# HV_DCDC_4-22-2016.net
KiCad netlist of a schematic drawn in EAGLE
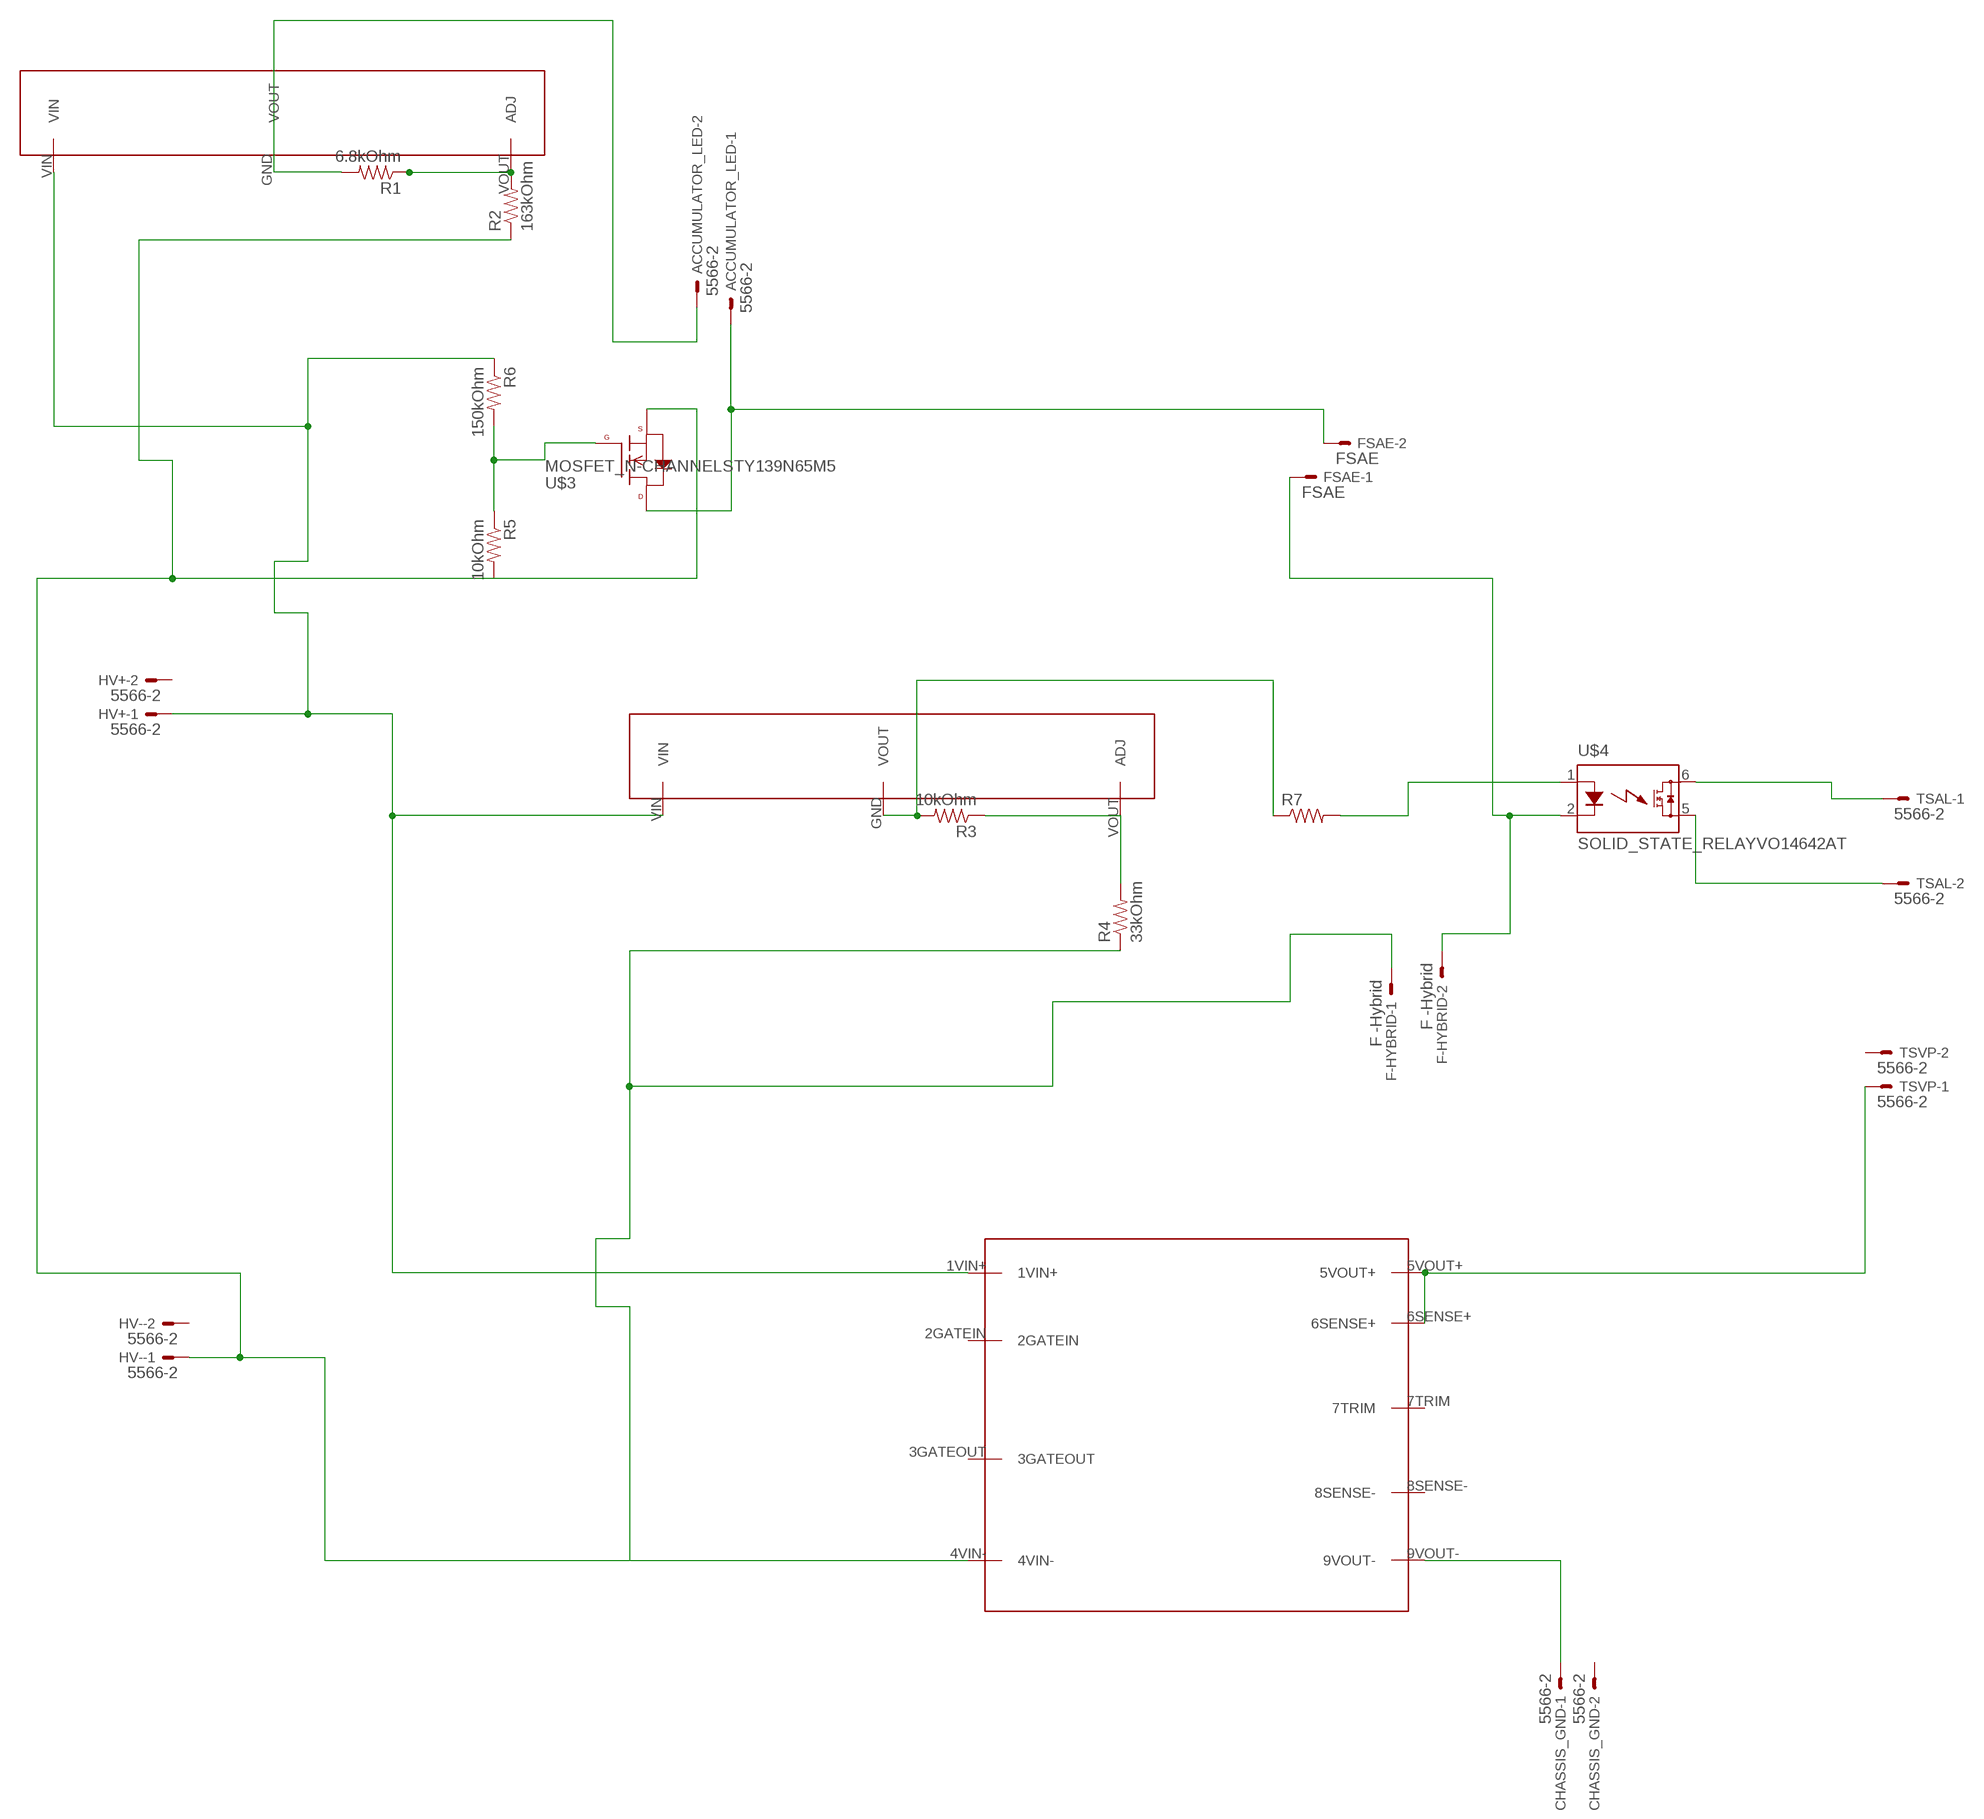
[diagram p0: schematic, sheet 1]

(export (version "E")
  (design (tool "Eeschema 10.0.6"))
  (components
    (comp (ref "ACCUMULATOR_LED")
      (value "5566-2")
      (footprint "eagle-import:5566-2")
      (libsource (lib "eagle-import") (part "5566-2"))
    )
    (comp (ref "CHASSIS_GND")
      (value "5566-2")
      (footprint "eagle-import:5566-2")
      (libsource (lib "eagle-import") (part "5566-2"))
    )
    (comp (ref "F-HYBRID")
      (value "F -Hybrid")
      (footprint "eagle-import:5566-2")
      (libsource (lib "eagle-import") (part "5566-2"))
    )
    (comp (ref "FSAE")
      (value "FSAE")
      (footprint "eagle-import:5566-2")
      (libsource (lib "eagle-import") (part "5566-2"))
    )
    (comp (ref "HV+")
      (value "5566-2")
      (footprint "eagle-import:5566-2")
      (libsource (lib "eagle-import") (part "5566-2"))
    )
    (comp (ref "HV-")
      (value "5566-2")
      (footprint "eagle-import:5566-2")
      (libsource (lib "eagle-import") (part "5566-2"))
    )
    (comp (ref "R1")
      (value "6.8kOhm")
      (footprint "eagle-import:AXIAL-0.3")
      (libsource (lib "eagle-import") (part "RESISTORAXIAL-0.3"))
    )
    (comp (ref "R2")
      (value "163kOhm")
      (footprint "eagle-import:AXIAL-0.3")
      (libsource (lib "eagle-import") (part "RESISTORAXIAL-0.3"))
    )
    (comp (ref "R3")
      (value "10kOhm")
      (footprint "eagle-import:AXIAL-0.3")
      (libsource (lib "eagle-import") (part "RESISTORAXIAL-0.3"))
    )
    (comp (ref "R4")
      (value "33kOhm")
      (footprint "eagle-import:AXIAL-0.3")
      (libsource (lib "eagle-import") (part "RESISTORAXIAL-0.3"))
    )
    (comp (ref "R5")
      (value "10kOhm")
      (footprint "eagle-import:AXIAL-0.3")
      (libsource (lib "eagle-import") (part "RESISTORAXIAL-0.3"))
    )
    (comp (ref "R6")
      (value "150kOhm")
      (footprint "eagle-import:AXIAL-0.3")
      (libsource (lib "eagle-import") (part "RESISTORAXIAL-0.3"))
    )
    (comp (ref "R7")
      (value "RESISTORAXIAL-0.3")
      (footprint "eagle-import:AXIAL-0.3")
      (libsource (lib "eagle-import") (part "RESISTORAXIAL-0.3"))
    )
    (comp (ref "TSAL")
      (value "5566-2")
      (footprint "eagle-import:5566-2")
      (libsource (lib "eagle-import") (part "5566-2"))
    )
    (comp (ref "TSVP")
      (value "5566-2")
      (footprint "eagle-import:5566-2")
      (libsource (lib "eagle-import") (part "5566-2"))
    )
    (comp (ref "U$3")
      (value "MOSFET_N-CHANNELSTY139N65M5")
      (footprint "eagle-import:TO-264_MAX247")
      (libsource (lib "eagle-import") (part "MOSFET_N-CHANNELSTY139N65M5"))
    )
    (comp (ref "U$4")
      (value "SOLID_STATE_RELAYVO14642AT")
      (footprint "eagle-import:DIL06")
      (libsource (lib "eagle-import") (part "SOLID_STATE_RELAYVO14642AT"))
    )
    (comp (ref "U$5")
      (value "HV_DCDC_NEW")
      (footprint "eagle-import:HV_DCDC_NEW")
      (libsource (lib "eagle-import") (part "HV_DCDC_NEW"))
    )
    (comp (ref "U$6")
      (value "HV_LIN_REG")
      (footprint "eagle-import:HV_LIN_REG14MM")
      (libsource (lib "eagle-import") (part "HV_LIN_REG"))
    )
    (comp (ref "U$7")
      (value "HV_LIN_REG")
      (footprint "eagle-import:HV_LIN_REG14MM")
      (libsource (lib "eagle-import") (part "HV_LIN_REG"))
    )
  )
  (nets
    (net (code "1") (name "Net-(ACCUMULATOR_LEDA-S)") (class "Default")
      (node (ref "ACCUMULATOR_LED") (pin "1") (pinfunction "S_1") (pintype "passive"))
      (node (ref "FSAE") (pin "2") (pinfunction "S_2") (pintype "passive"))
      (node (ref "U$3") (pin "P2") (pinfunction "DRAIN_P2") (pintype "passive"))
    )
    (net (code "2") (name "Net-(ACCUMULATOR_LEDB-S)") (class "Default")
      (node (ref "ACCUMULATOR_LED") (pin "2") (pinfunction "S_2") (pintype "passive"))
      (node (ref "R1") (pin "P$2") (pinfunction "2_P$2") (pintype "passive"))
      (node (ref "U$7") (pin "GND") (pinfunction "VOUT_GND") (pintype "bidirectional"))
    )
    (net (code "3") (name "Net-(CHASSIS_GNDA-S)") (class "Default")
      (node (ref "CHASSIS_GND") (pin "1") (pinfunction "S_1") (pintype "passive"))
      (node (ref "U$5") (pin "9VOUT-") (pinfunction "9VOUT-_9VOUT-") (pintype "bidirectional"))
    )
    (net (code "4") (name "Net-(F-HYBRIDA-S)") (class "Default")
      (node (ref "F-HYBRID") (pin "1") (pinfunction "S_1") (pintype "passive"))
      (node (ref "HV-") (pin "1") (pinfunction "S_1") (pintype "passive"))
      (node (ref "R2") (pin "P$1") (pinfunction "1_P$1") (pintype "passive"))
      (node (ref "R4") (pin "P$1") (pinfunction "1_P$1") (pintype "passive"))
      (node (ref "R5") (pin "P$2") (pinfunction "2_P$2") (pintype "passive"))
      (node (ref "U$3") (pin "P3") (pinfunction "SOURCE_P3") (pintype "passive"))
      (node (ref "U$5") (pin "4VIN-") (pinfunction "4VIN-_4VIN-") (pintype "bidirectional"))
    )
    (net (code "5") (name "Net-(F-HYBRIDB-S)") (class "Default")
      (node (ref "F-HYBRID") (pin "2") (pinfunction "S_2") (pintype "passive"))
      (node (ref "FSAE") (pin "1") (pinfunction "S_1") (pintype "passive"))
      (node (ref "U$4") (pin "2") (pinfunction "LED-_2") (pintype "passive"))
    )
    (net (code "6") (name "Net-(HV+A-S)") (class "Default")
      (node (ref "HV+") (pin "1") (pinfunction "S_1") (pintype "passive"))
      (node (ref "R6") (pin "P$1") (pinfunction "1_P$1") (pintype "passive"))
      (node (ref "U$5") (pin "1VIN+") (pinfunction "1VIN+_1VIN+") (pintype "bidirectional"))
      (node (ref "U$6") (pin "VIN") (pinfunction "VIN_VIN") (pintype "bidirectional"))
      (node (ref "U$7") (pin "VIN") (pinfunction "VIN_VIN") (pintype "bidirectional"))
    )
    (net (code "7") (name "Net-(R1-1)") (class "Default")
      (node (ref "R1") (pin "P$1") (pinfunction "1_P$1") (pintype "passive"))
      (node (ref "R2") (pin "P$2") (pinfunction "2_P$2") (pintype "passive"))
      (node (ref "U$7") (pin "VOUT") (pinfunction "ADJ_VOUT") (pintype "bidirectional"))
    )
    (net (code "8") (name "Net-(R3-1)") (class "Default")
      (node (ref "R3") (pin "P$1") (pinfunction "1_P$1") (pintype "passive"))
      (node (ref "R4") (pin "P$2") (pinfunction "2_P$2") (pintype "passive"))
      (node (ref "U$6") (pin "VOUT") (pinfunction "ADJ_VOUT") (pintype "bidirectional"))
    )
    (net (code "9") (name "Net-(R3-2)") (class "Default")
      (node (ref "R3") (pin "P$2") (pinfunction "2_P$2") (pintype "passive"))
      (node (ref "R7") (pin "P$1") (pinfunction "1_P$1") (pintype "passive"))
      (node (ref "U$6") (pin "GND") (pinfunction "VOUT_GND") (pintype "bidirectional"))
    )
    (net (code "10") (name "Net-(R5-1)") (class "Default")
      (node (ref "R5") (pin "P$1") (pinfunction "1_P$1") (pintype "passive"))
      (node (ref "R6") (pin "P$2") (pinfunction "2_P$2") (pintype "passive"))
      (node (ref "U$3") (pin "P1") (pinfunction "GATE_P1") (pintype "passive"))
    )
    (net (code "11") (name "Net-(R7-2)") (class "Default")
      (node (ref "R7") (pin "P$2") (pinfunction "2_P$2") (pintype "passive"))
      (node (ref "U$4") (pin "1") (pinfunction "LED+_1") (pintype "passive"))
    )
    (net (code "12") (name "Net-(TSALA-S)") (class "Default")
      (node (ref "TSAL") (pin "1") (pinfunction "S_1") (pintype "passive"))
      (node (ref "U$4") (pin "6") (pinfunction "IO1_6") (pintype "passive"))
    )
    (net (code "13") (name "Net-(TSALB-S)") (class "Default")
      (node (ref "TSAL") (pin "2") (pinfunction "S_2") (pintype "passive"))
      (node (ref "U$4") (pin "5") (pinfunction "IO2_5") (pintype "passive"))
    )
    (net (code "14") (name "Net-(TSVPA-S)") (class "Default")
      (node (ref "TSVP") (pin "1") (pinfunction "S_1") (pintype "passive"))
      (node (ref "U$5") (pin "5VOUT+") (pinfunction "5VOUT+_5VOUT+") (pintype "bidirectional"))
      (node (ref "U$5") (pin "6SENSE+") (pinfunction "6SENSE+_6SENSE+") (pintype "bidirectional"))
    )
    (net (code "15") (name "unconnected-(CHASSIS_GNDB-S-Pad2)") (class "Default")
      (node (ref "CHASSIS_GND") (pin "2") (pinfunction "S_2") (pintype "passive"))
    )
    (net (code "16") (name "unconnected-(HV+B-S-Pad2)") (class "Default")
      (node (ref "HV+") (pin "2") (pinfunction "S_2") (pintype "passive"))
    )
    (net (code "17") (name "unconnected-(HV-B-S-Pad2)") (class "Default")
      (node (ref "HV-") (pin "2") (pinfunction "S_2") (pintype "passive"))
    )
    (net (code "18") (name "unconnected-(TSVPB-S-Pad2)") (class "Default")
      (node (ref "TSVP") (pin "2") (pinfunction "S_2") (pintype "passive"))
    )
    (net (code "19") (name "unconnected-(U$5-Pad2GATEIN)") (class "Default")
      (node (ref "U$5") (pin "2GATEIN") (pinfunction "2GATEIN_2GATEIN") (pintype "bidirectional"))
    )
    (net (code "20") (name "unconnected-(U$5-Pad3GATEOUT)") (class "Default")
      (node (ref "U$5") (pin "3GATEOUT") (pinfunction "3GATEOUT_3GATEOUT") (pintype "bidirectional"))
    )
    (net (code "21") (name "unconnected-(U$5-Pad7TRIM)") (class "Default")
      (node (ref "U$5") (pin "7TRIM") (pinfunction "7TRIM_7TRIM") (pintype "bidirectional"))
    )
    (net (code "22") (name "unconnected-(U$5-Pad8SENSE-)") (class "Default")
      (node (ref "U$5") (pin "8SENSE-") (pinfunction "8SENSE-_8SENSE-") (pintype "bidirectional"))
    )
  )
)
